# komp_podnap.net
KiCad netlist of a schematic drawn in EAGLE
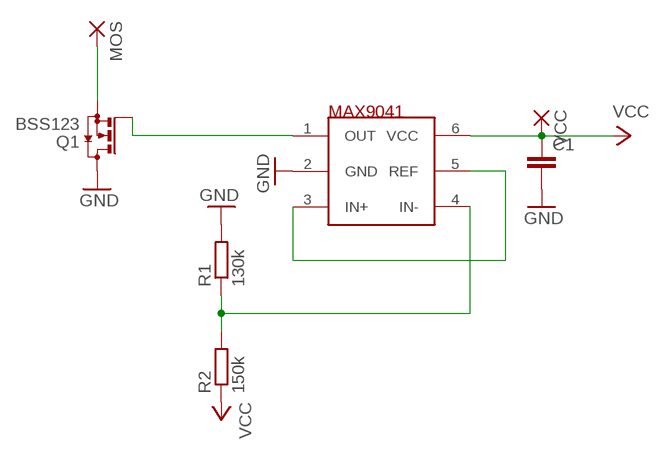
[diagram p0: schematic, sheet 1]

(export (version "E")
  (design (tool "Eeschema 10.0.6"))
  (components
    (comp (ref "C1")
      (value "C-EUC0805")
      (footprint "eagle-import:C0805")
      (libsource (lib "eagle-import") (part "C-EUC0805"))
    )
    (comp (ref "MOS")
      (value "2,54/0,8")
      (footprint "eagle-import:2,54_0,8")
      (libsource (lib "eagle-import") (part "2,54/0,8"))
    )
    (comp (ref "Q1")
      (value "BSS123")
      (footprint "eagle-import:SOT23")
      (libsource (lib "eagle-import") (part "BSS123"))
    )
    (comp (ref "R1")
      (value "130k")
      (footprint "eagle-import:M0805")
      (libsource (lib "eagle-import") (part "R-EU_M0805"))
    )
    (comp (ref "R2")
      (value "150k")
      (footprint "eagle-import:M0805")
      (libsource (lib "eagle-import") (part "R-EU_M0805"))
    )
    (comp (ref "U$1")
      (value "MAX9041")
      (footprint "eagle-import:SOT23-6")
      (libsource (lib "eagle-import") (part "MAX9041"))
    )
    (comp (ref "VCC")
      (value "2,54/0,8")
      (footprint "eagle-import:2,54_0,8")
      (libsource (lib "eagle-import") (part "2,54/0,8"))
    )
  )
  (nets
    (net (code "1") (name "GND") (class "Default")
      (node (ref "C1") (pin "2") (pinfunction "2_2") (pintype "passive"))
      (node (ref "Q1") (pin "3") (pinfunction "D_3") (pintype "passive"))
      (node (ref "R1") (pin "2") (pinfunction "2_2") (pintype "passive"))
      (node (ref "U$1") (pin "2") (pinfunction "GND_2") (pintype "bidirectional"))
    )
    (net (code "2") (name "Net-(MOS-P)") (class "Default")
      (node (ref "MOS") (pin "1") (pinfunction "P_1") (pintype "passive"))
      (node (ref "Q1") (pin "2") (pinfunction "S_2") (pintype "passive"))
    )
    (net (code "3") (name "Net-(Q1-G)") (class "Default")
      (node (ref "Q1") (pin "1") (pinfunction "G_1") (pintype "passive"))
      (node (ref "U$1") (pin "1") (pinfunction "OUT_1") (pintype "bidirectional"))
    )
    (net (code "4") (name "Net-(U$1-IN+)") (class "Default")
      (node (ref "U$1") (pin "3") (pinfunction "IN+_3") (pintype "bidirectional"))
      (node (ref "U$1") (pin "5") (pinfunction "REF_5") (pintype "bidirectional"))
    )
    (net (code "5") (name "Net-(U$1-IN-)") (class "Default")
      (node (ref "R1") (pin "1") (pinfunction "1_1") (pintype "passive"))
      (node (ref "R2") (pin "2") (pinfunction "2_2") (pintype "passive"))
      (node (ref "U$1") (pin "4") (pinfunction "IN-_4") (pintype "bidirectional"))
    )
    (net (code "6") (name "VCC") (class "Default")
      (node (ref "C1") (pin "1") (pinfunction "1_1") (pintype "passive"))
      (node (ref "R2") (pin "1") (pinfunction "1_1") (pintype "passive"))
      (node (ref "U$1") (pin "6") (pinfunction "VCC_6") (pintype "bidirectional"))
      (node (ref "VCC") (pin "1") (pinfunction "P_1") (pintype "passive"))
    )
  )
)
